# Adaptor.net
KiCad netlist of a schematic drawn in EAGLE
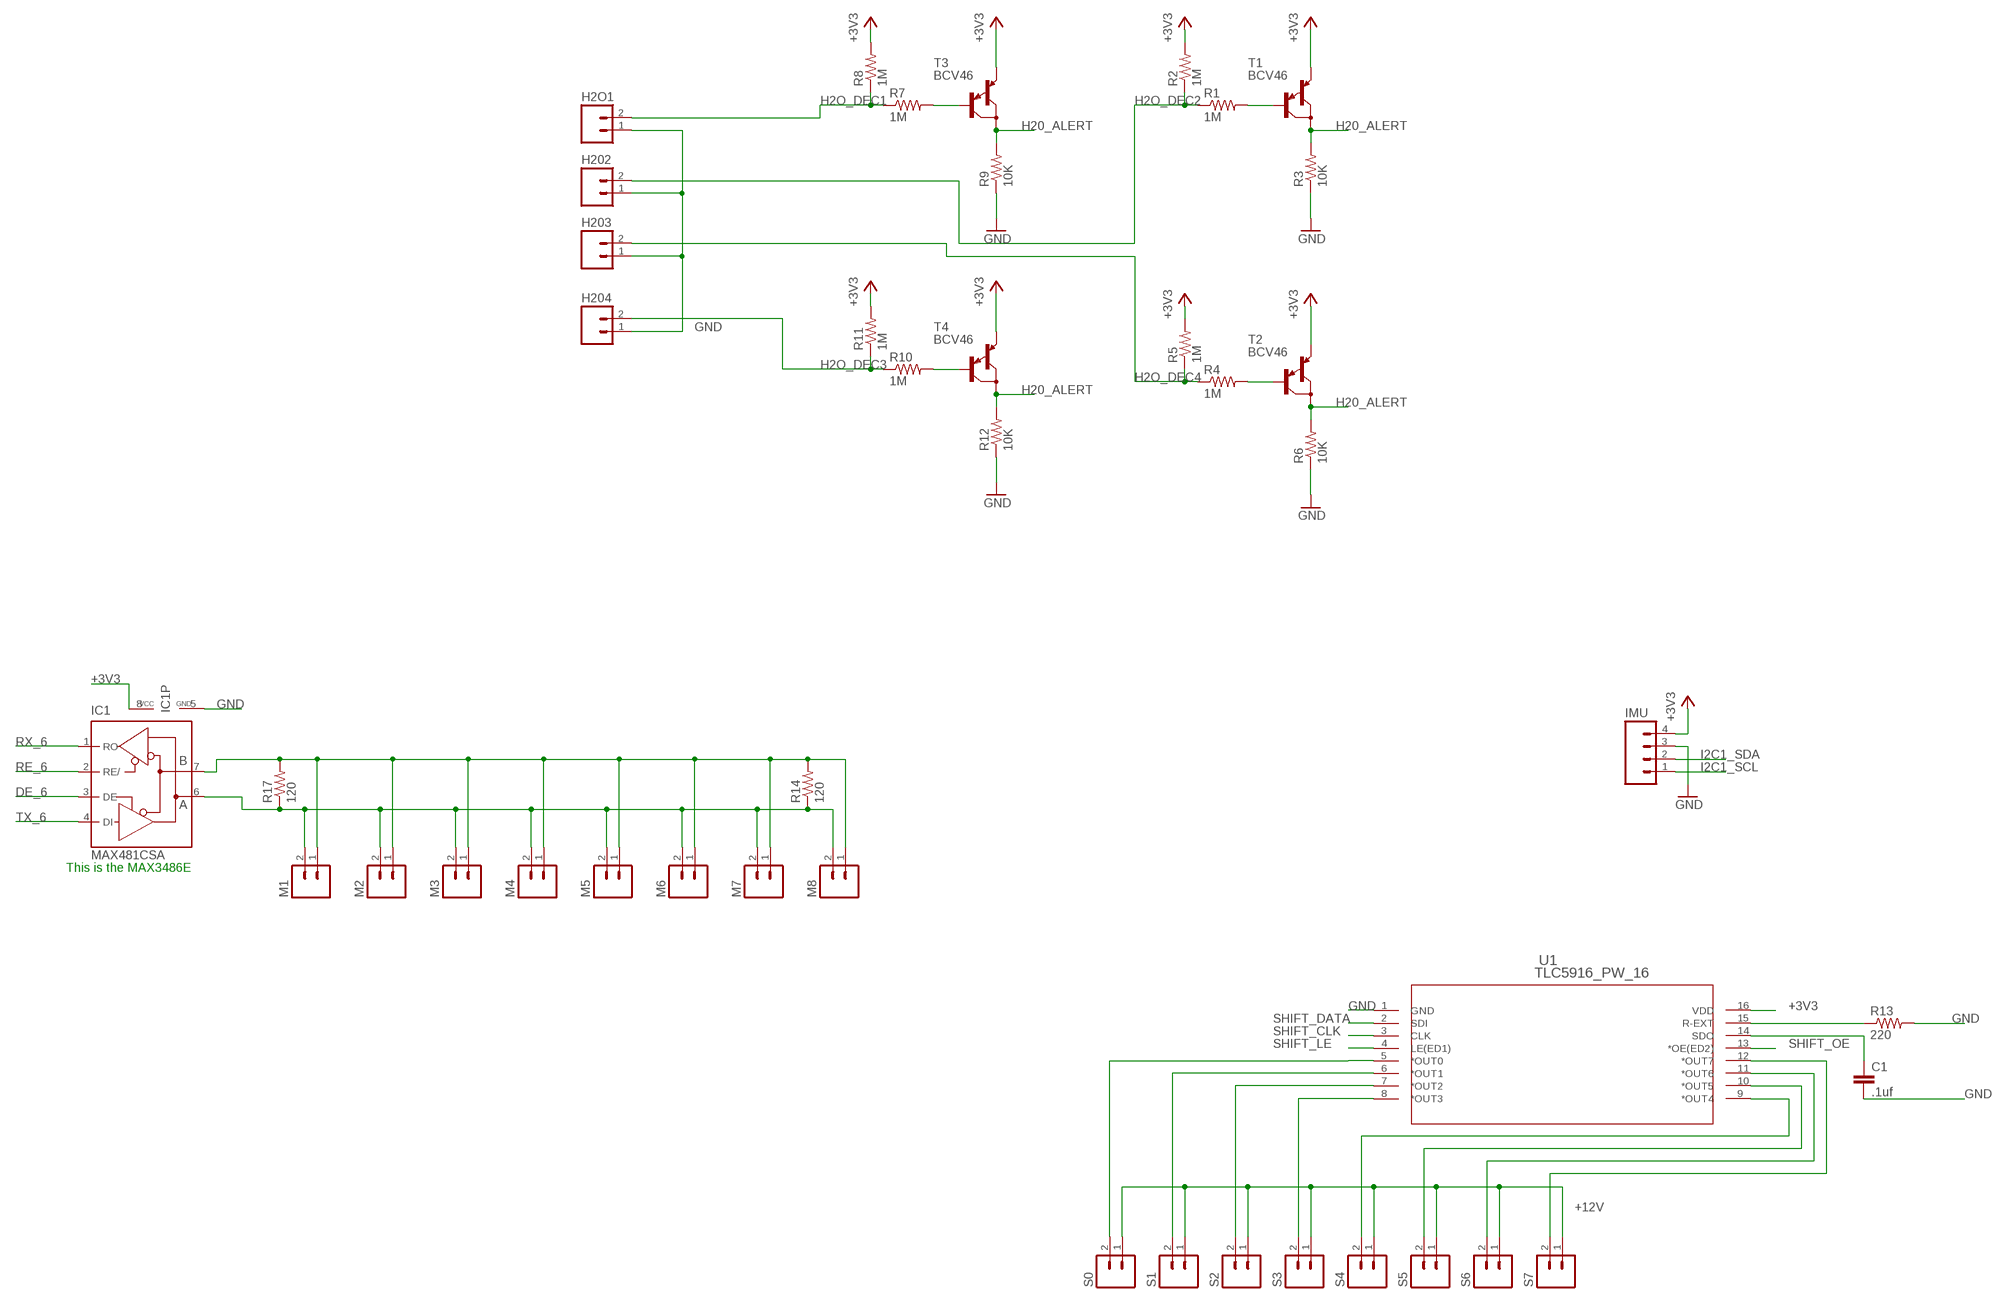
[diagram p0: schematic, sheet 1, part 1 of 2]
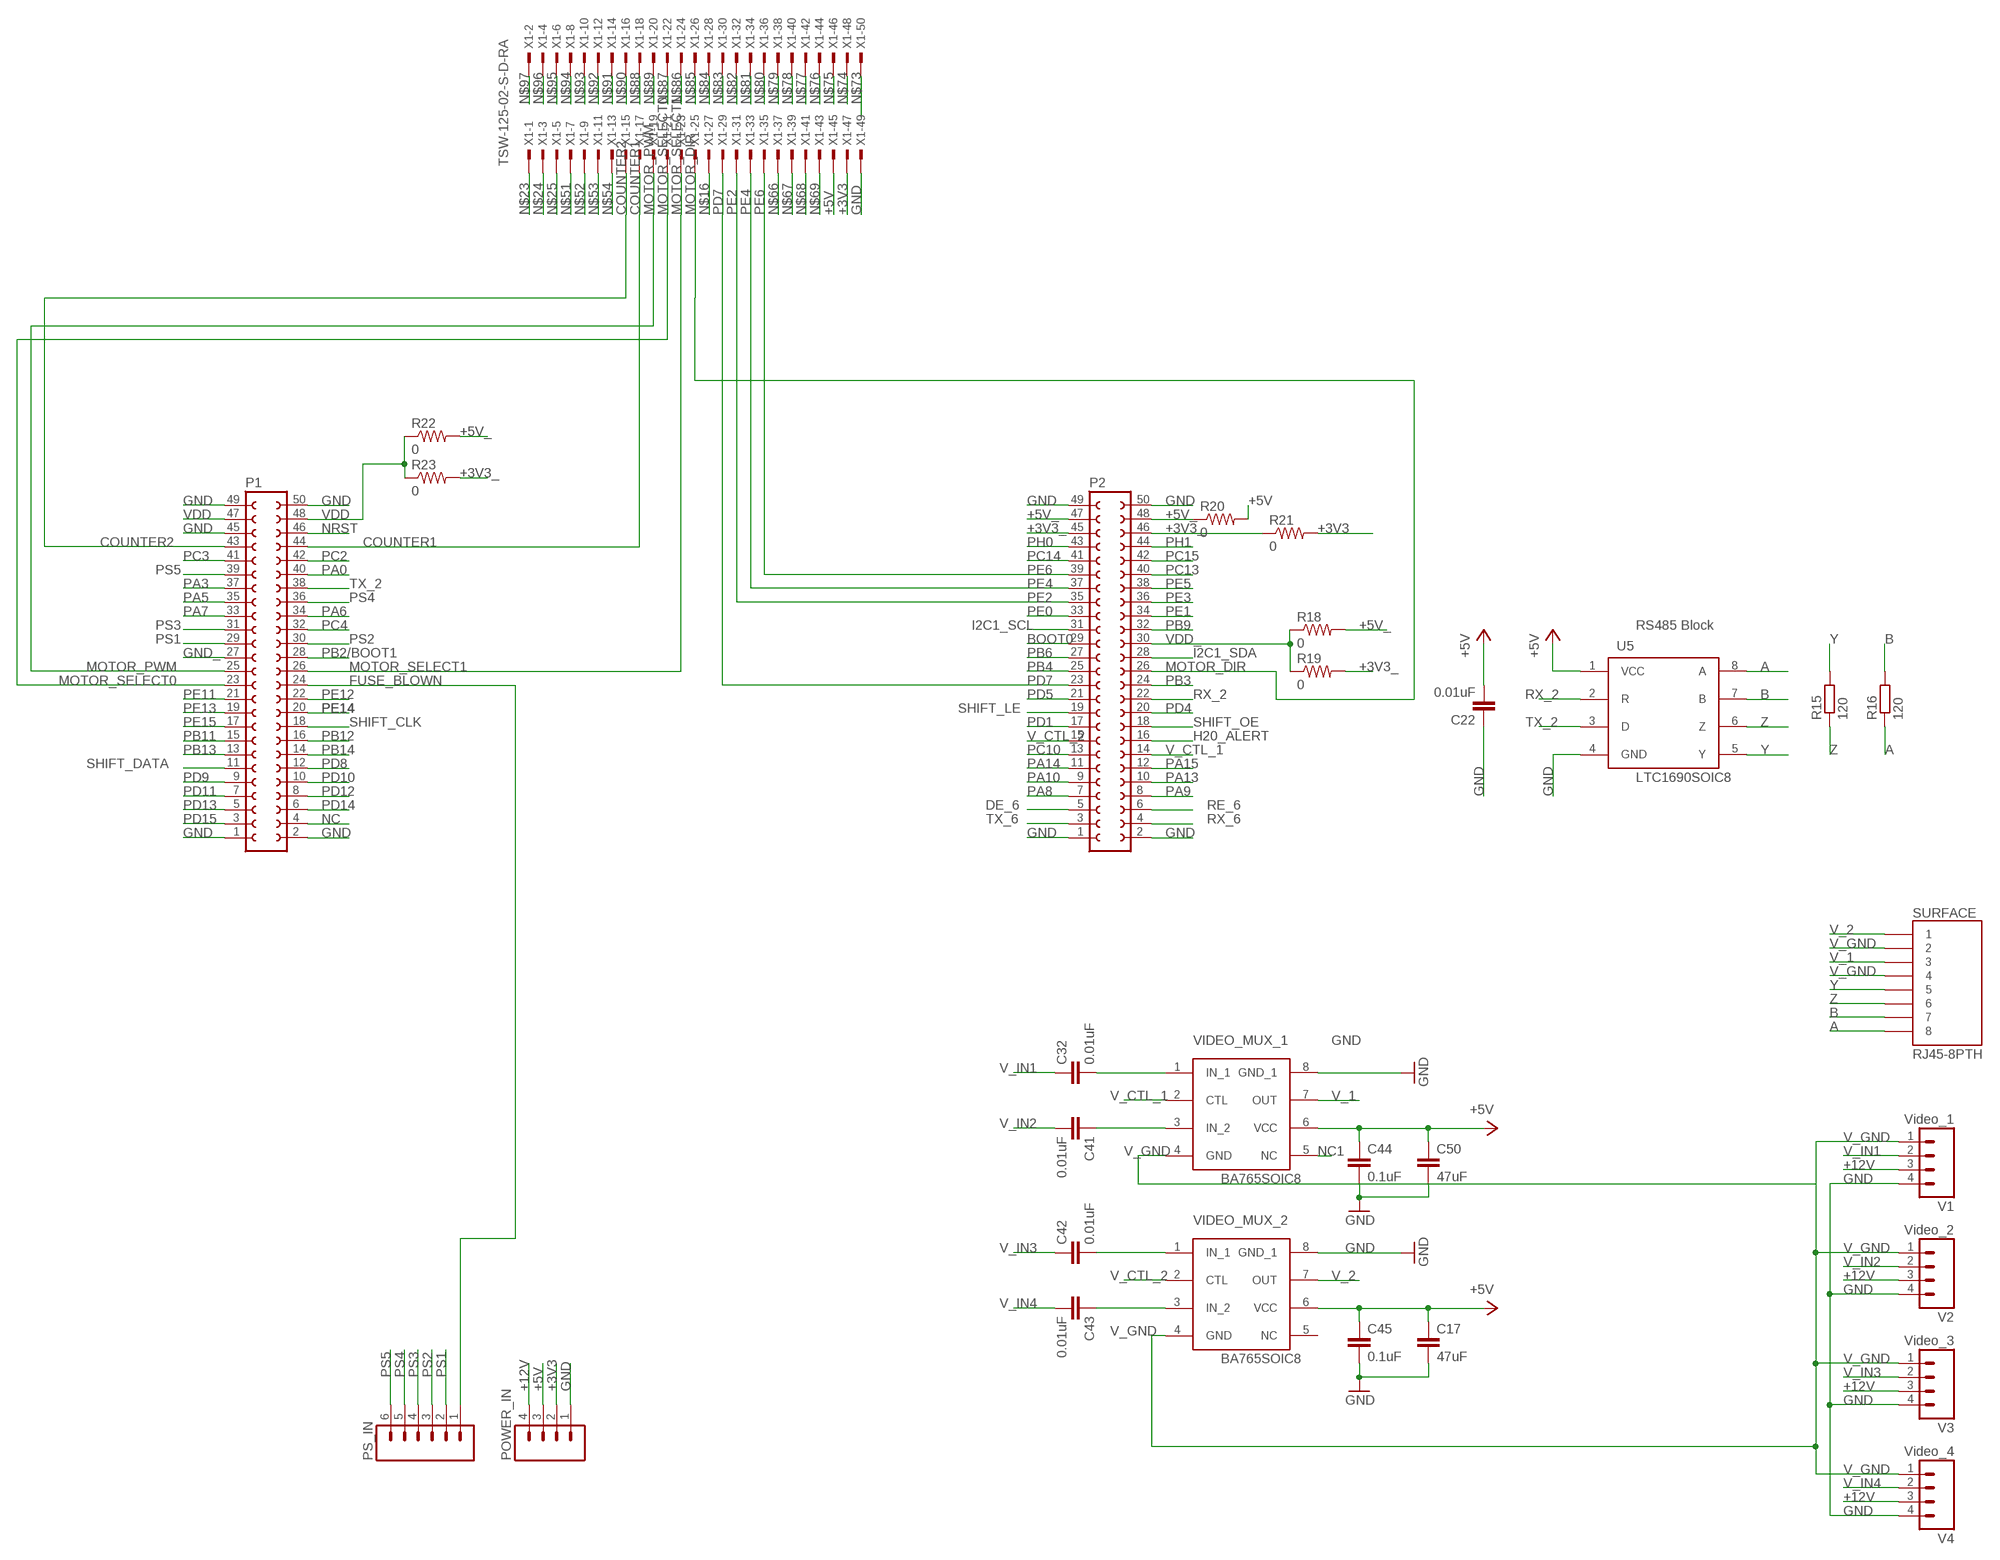
[diagram p1: schematic, sheet 1, part 2 of 2]

(export (version "E")
  (design (tool "Eeschema 10.0.6"))
  (components
    (comp (ref "C1")
      (value ".1uf")
      (footprint "eagle-import:0805")
      (libsource (lib "eagle-import") (part "CAP0805"))
    )
    (comp (ref "C17")
      (value "47uF")
      (footprint "eagle-import:C1206")
      (fields (field (name "PARTNO") "490-5528-1-ND"))
      (libsource (lib "eagle-import") (part "C-EUC1206"))
    )
    (comp (ref "C22")
      (value "0.01uF")
      (footprint "eagle-import:C0603")
      (fields (field (name "PARTNO") "478-1227-1-ND"))
      (libsource (lib "eagle-import") (part "C-EUC0603"))
    )
    (comp (ref "C32")
      (value "0.01uF")
      (footprint "eagle-import:C0603")
      (fields (field (name "PARTNO") "478-1227-1-ND"))
      (libsource (lib "eagle-import") (part "C-EUC0603"))
    )
    (comp (ref "C41")
      (value "0.01uF")
      (footprint "eagle-import:C0603")
      (fields (field (name "PARTNO") "478-1227-1-ND"))
      (libsource (lib "eagle-import") (part "C-EUC0603"))
    )
    (comp (ref "C42")
      (value "0.01uF")
      (footprint "eagle-import:C0603")
      (fields (field (name "PARTNO") "478-1227-1-ND"))
      (libsource (lib "eagle-import") (part "C-EUC0603"))
    )
    (comp (ref "C43")
      (value "0.01uF")
      (footprint "eagle-import:C0603")
      (fields (field (name "PARTNO") "478-1227-1-ND"))
      (libsource (lib "eagle-import") (part "C-EUC0603"))
    )
    (comp (ref "C44")
      (value "0.1uF")
      (footprint "eagle-import:C0603")
      (fields (field (name "PARTNO") "311-1344-1-ND"))
      (libsource (lib "eagle-import") (part "C-EUC0603"))
    )
    (comp (ref "C45")
      (value "0.1uF")
      (footprint "eagle-import:C0603")
      (fields (field (name "PARTNO") "311-1344-1-ND"))
      (libsource (lib "eagle-import") (part "C-EUC0603"))
    )
    (comp (ref "C50")
      (value "47uF")
      (footprint "eagle-import:C1206")
      (fields (field (name "PARTNO") "490-5528-1-ND"))
      (libsource (lib "eagle-import") (part "C-EUC1206"))
    )
    (comp (ref "H2O1")
      (value "M02PTH")
      (footprint "eagle-import:1X02")
      (libsource (lib "eagle-import") (part "M02PTH"))
    )
    (comp (ref "H202")
      (value "M02PTH")
      (footprint "eagle-import:1X02")
      (libsource (lib "eagle-import") (part "M02PTH"))
    )
    (comp (ref "H203")
      (value "M02PTH")
      (footprint "eagle-import:1X02")
      (libsource (lib "eagle-import") (part "M02PTH"))
    )
    (comp (ref "H204")
      (value "M02PTH")
      (footprint "eagle-import:1X02")
      (libsource (lib "eagle-import") (part "M02PTH"))
    )
    (comp (ref "IC1")
      (value "MAX481CSA")
      (footprint "eagle-import:SO08")
      (fields (field (name "MF") "MAXIM"))
      (libsource (lib "eagle-import") (part "MAX481CSA"))
    )
    (comp (ref "IMU")
      (value "M04PTH")
      (footprint "eagle-import:1X04")
      (libsource (lib "eagle-import") (part "M04PTH"))
    )
    (comp (ref "M1")
      (value "M02PTH")
      (footprint "eagle-import:1X02")
      (libsource (lib "eagle-import") (part "M02PTH"))
    )
    (comp (ref "M2")
      (value "M02PTH")
      (footprint "eagle-import:1X02")
      (libsource (lib "eagle-import") (part "M02PTH"))
    )
    (comp (ref "M3")
      (value "M02PTH")
      (footprint "eagle-import:1X02")
      (libsource (lib "eagle-import") (part "M02PTH"))
    )
    (comp (ref "M4")
      (value "M02PTH")
      (footprint "eagle-import:1X02")
      (libsource (lib "eagle-import") (part "M02PTH"))
    )
    (comp (ref "M5")
      (value "M02PTH")
      (footprint "eagle-import:1X02")
      (libsource (lib "eagle-import") (part "M02PTH"))
    )
    (comp (ref "M6")
      (value "M02PTH")
      (footprint "eagle-import:1X02")
      (libsource (lib "eagle-import") (part "M02PTH"))
    )
    (comp (ref "M7")
      (value "M02PTH")
      (footprint "eagle-import:1X02")
      (libsource (lib "eagle-import") (part "M02PTH"))
    )
    (comp (ref "M8")
      (value "M02PTH")
      (footprint "eagle-import:1X02")
      (libsource (lib "eagle-import") (part "M02PTH"))
    )
    (comp (ref "P1")
      (value "FE25-2")
      (footprint "eagle-import:FE25-2")
      (libsource (lib "eagle-import") (part "FE25-2"))
    )
    (comp (ref "P2")
      (value "FE25-2")
      (footprint "eagle-import:FE25-2")
      (libsource (lib "eagle-import") (part "FE25-2"))
    )
    (comp (ref "POWER_IN")
      (value "M04PTH")
      (footprint "eagle-import:1X04")
      (libsource (lib "eagle-import") (part "M04PTH"))
    )
    (comp (ref "PS_IN")
      (value "M06SIP")
      (footprint "eagle-import:1X06")
      (libsource (lib "eagle-import") (part "M06SIP"))
    )
    (comp (ref "R1")
      (value "1M")
      (footprint "eagle-import:0805")
      (libsource (lib "eagle-import") (part "SparkFun-Resistors_RESISTOR0805-RES"))
    )
    (comp (ref "R2")
      (value "1M")
      (footprint "eagle-import:0805")
      (libsource (lib "eagle-import") (part "SparkFun-Resistors_RESISTOR0805-RES"))
    )
    (comp (ref "R3")
      (value "10K")
      (footprint "eagle-import:0805")
      (libsource (lib "eagle-import") (part "SparkFun-Resistors_RESISTOR0805-RES"))
    )
    (comp (ref "R4")
      (value "1M")
      (footprint "eagle-import:0805")
      (libsource (lib "eagle-import") (part "SparkFun-Resistors_RESISTOR0805-RES"))
    )
    (comp (ref "R5")
      (value "1M")
      (footprint "eagle-import:0805")
      (libsource (lib "eagle-import") (part "SparkFun-Resistors_RESISTOR0805-RES"))
    )
    (comp (ref "R6")
      (value "10K")
      (footprint "eagle-import:0805")
      (libsource (lib "eagle-import") (part "SparkFun-Resistors_RESISTOR0805-RES"))
    )
    (comp (ref "R7")
      (value "1M")
      (footprint "eagle-import:0805")
      (libsource (lib "eagle-import") (part "SparkFun-Resistors_RESISTOR0805-RES"))
    )
    (comp (ref "R8")
      (value "1M")
      (footprint "eagle-import:0805")
      (libsource (lib "eagle-import") (part "SparkFun-Resistors_RESISTOR0805-RES"))
    )
    (comp (ref "R9")
      (value "10K")
      (footprint "eagle-import:0805")
      (libsource (lib "eagle-import") (part "SparkFun-Resistors_RESISTOR0805-RES"))
    )
    (comp (ref "R10")
      (value "1M")
      (footprint "eagle-import:0805")
      (libsource (lib "eagle-import") (part "SparkFun-Resistors_RESISTOR0805-RES"))
    )
    (comp (ref "R11")
      (value "1M")
      (footprint "eagle-import:0805")
      (libsource (lib "eagle-import") (part "SparkFun-Resistors_RESISTOR0805-RES"))
    )
    (comp (ref "R12")
      (value "10K")
      (footprint "eagle-import:0805")
      (libsource (lib "eagle-import") (part "SparkFun-Resistors_RESISTOR0805-RES"))
    )
    (comp (ref "R13")
      (value "220")
      (footprint "eagle-import:0805")
      (libsource (lib "eagle-import") (part "RESISTOR0805-RES"))
    )
    (comp (ref "R14")
      (value "120")
      (footprint "eagle-import:0805")
      (libsource (lib "eagle-import") (part "RESISTOR0805-RES"))
    )
    (comp (ref "R15")
      (value "120")
      (footprint "eagle-import:R0603")
      (libsource (lib "eagle-import") (part "R-EU_R0603"))
    )
    (comp (ref "R16")
      (value "120")
      (footprint "eagle-import:R0603")
      (libsource (lib "eagle-import") (part "R-EU_R0603"))
    )
    (comp (ref "R17")
      (value "120")
      (footprint "eagle-import:0805")
      (libsource (lib "eagle-import") (part "RESISTOR0805-RES"))
    )
    (comp (ref "R18")
      (value "0")
      (footprint "eagle-import:0805")
      (libsource (lib "eagle-import") (part "SparkFun-Resistors_RESISTOR0805-RES"))
    )
    (comp (ref "R19")
      (value "0")
      (footprint "eagle-import:0805")
      (libsource (lib "eagle-import") (part "SparkFun-Resistors_RESISTOR0805-RES"))
    )
    (comp (ref "R20")
      (value "0")
      (footprint "eagle-import:0805")
      (libsource (lib "eagle-import") (part "SparkFun-Resistors_RESISTOR0805-RES"))
    )
    (comp (ref "R21")
      (value "0")
      (footprint "eagle-import:0805")
      (libsource (lib "eagle-import") (part "SparkFun-Resistors_RESISTOR0805-RES"))
    )
    (comp (ref "R22")
      (value "0")
      (footprint "eagle-import:0805")
      (libsource (lib "eagle-import") (part "SparkFun-Resistors_RESISTOR0805-RES"))
    )
    (comp (ref "R23")
      (value "0")
      (footprint "eagle-import:0805")
      (libsource (lib "eagle-import") (part "SparkFun-Resistors_RESISTOR0805-RES"))
    )
    (comp (ref "S0")
      (value "M02PTH")
      (footprint "eagle-import:1X02")
      (libsource (lib "eagle-import") (part "M02PTH"))
    )
    (comp (ref "S1")
      (value "M02PTH")
      (footprint "eagle-import:1X02")
      (libsource (lib "eagle-import") (part "M02PTH"))
    )
    (comp (ref "S2")
      (value "M02PTH")
      (footprint "eagle-import:1X02")
      (libsource (lib "eagle-import") (part "M02PTH"))
    )
    (comp (ref "S3")
      (value "M02PTH")
      (footprint "eagle-import:1X02")
      (libsource (lib "eagle-import") (part "M02PTH"))
    )
    (comp (ref "S4")
      (value "M02PTH")
      (footprint "eagle-import:1X02")
      (libsource (lib "eagle-import") (part "M02PTH"))
    )
    (comp (ref "S5")
      (value "M02PTH")
      (footprint "eagle-import:1X02")
      (libsource (lib "eagle-import") (part "M02PTH"))
    )
    (comp (ref "S6")
      (value "M02PTH")
      (footprint "eagle-import:1X02")
      (libsource (lib "eagle-import") (part "M02PTH"))
    )
    (comp (ref "S7")
      (value "M02PTH")
      (footprint "eagle-import:1X02")
      (libsource (lib "eagle-import") (part "M02PTH"))
    )
    (comp (ref "SURFACE")
      (value "RJ45-8PTH")
      (footprint "eagle-import:RJ45-8")
      (libsource (lib "eagle-import") (part "RJ45-8PTH"))
    )
    (comp (ref "T1")
      (value "BCV46")
      (footprint "eagle-import:SOT23-BEC")
      (libsource (lib "eagle-import") (part "-PNP_DARL-SOT23-BECMMBTA64LT1"))
    )
    (comp (ref "T2")
      (value "BCV46")
      (footprint "eagle-import:SOT23-BEC")
      (libsource (lib "eagle-import") (part "-PNP_DARL-SOT23-BECMMBTA64LT1"))
    )
    (comp (ref "T3")
      (value "BCV46")
      (footprint "eagle-import:SOT23-BEC")
      (libsource (lib "eagle-import") (part "-PNP_DARL-SOT23-BECMMBTA64LT1"))
    )
    (comp (ref "T4")
      (value "BCV46")
      (footprint "eagle-import:SOT23-BEC")
      (libsource (lib "eagle-import") (part "-PNP_DARL-SOT23-BECMMBTA64LT1"))
    )
    (comp (ref "U1")
      (value "TLC5916_PW_16")
      (footprint "eagle-import:PW16")
      (fields
        (field (name "GENERIC_PART_NUMBER") "TLC5916")
        (field (name "MANUFACTURER") "Texas Instruments")
        (field (name "MANUFACTURER_PART_NUMBER") "tlc5916_pw_16")
      )
      (libsource (lib "eagle-import") (part "TLC5916_PW_16"))
    )
    (comp (ref "U5")
      (value "LTC1690SOIC8")
      (footprint "eagle-import:SOIC8")
      (libsource (lib "eagle-import") (part "LTC1690SOIC8"))
    )
    (comp (ref "V1")
      (value "Video_1")
      (footprint "eagle-import:1X04")
      (libsource (lib "eagle-import") (part "M04PTH"))
    )
    (comp (ref "V2")
      (value "Video_2")
      (footprint "eagle-import:1X04")
      (libsource (lib "eagle-import") (part "M04PTH"))
    )
    (comp (ref "V3")
      (value "Video_3")
      (footprint "eagle-import:1X04")
      (libsource (lib "eagle-import") (part "M04PTH"))
    )
    (comp (ref "V4")
      (value "Video_4")
      (footprint "eagle-import:1X04")
      (libsource (lib "eagle-import") (part "M04PTH"))
    )
    (comp (ref "VIDEO_MUX_1")
      (value "BA765SOIC8")
      (footprint "eagle-import:SOIC8")
      (libsource (lib "eagle-import") (part "BA765SOIC8"))
    )
    (comp (ref "VIDEO_MUX_2")
      (value "BA765SOIC8")
      (footprint "eagle-import:SOIC8")
      (libsource (lib "eagle-import") (part "BA765SOIC8"))
    )
    (comp (ref "X1")
      (value "TSW-125-02-S-D-RA")
      (footprint "eagle-import:TSW-125-02-S-D-RA")
      (libsource (lib "eagle-import") (part "TSW-125-02-S-D-RA"))
    )
  )
  (nets
    (net (code "1") (name "+3V3") (class "Default")
      (node (ref "IC1") (pin "8") (pinfunction "VCC_8") (pintype "power_in"))
      (node (ref "IMU") (pin "4") (pinfunction "4_4") (pintype "passive"))
      (node (ref "POWER_IN") (pin "2") (pinfunction "2_2") (pintype "passive"))
      (node (ref "R11") (pin "2") (pinfunction "2_2") (pintype "passive"))
      (node (ref "R2") (pin "2") (pinfunction "2_2") (pintype "passive"))
      (node (ref "R21") (pin "2") (pinfunction "2_2") (pintype "passive"))
      (node (ref "R5") (pin "2") (pinfunction "2_2") (pintype "passive"))
      (node (ref "R8") (pin "2") (pinfunction "2_2") (pintype "passive"))
      (node (ref "T1") (pin "E") (pinfunction "E_E") (pintype "passive"))
      (node (ref "T2") (pin "E") (pinfunction "E_E") (pintype "passive"))
      (node (ref "T3") (pin "E") (pinfunction "E_E") (pintype "passive"))
      (node (ref "T4") (pin "E") (pinfunction "E_E") (pintype "passive"))
      (node (ref "U1") (pin "16") (pinfunction "VDD_16") (pintype "power_in"))
      (node (ref "X1") (pin "47") (pinfunction "1_47") (pintype "passive"))
    )
    (net (code "2") (name "+5V") (class "Default")
      (node (ref "C17") (pin "1") (pinfunction "1_1") (pintype "passive"))
      (node (ref "C22") (pin "2") (pinfunction "2_2") (pintype "passive"))
      (node (ref "C44") (pin "1") (pinfunction "1_1") (pintype "passive"))
      (node (ref "C45") (pin "1") (pinfunction "1_1") (pintype "passive"))
      (node (ref "C50") (pin "1") (pinfunction "1_1") (pintype "passive"))
      (node (ref "POWER_IN") (pin "3") (pinfunction "3_3") (pintype "passive"))
      (node (ref "R20") (pin "2") (pinfunction "2_2") (pintype "passive"))
      (node (ref "U5") (pin "1") (pinfunction "VCC_1") (pintype "power_in"))
      (node (ref "VIDEO_MUX_1") (pin "6") (pinfunction "VCC_6") (pintype "bidirectional"))
      (node (ref "VIDEO_MUX_2") (pin "6") (pinfunction "VCC_6") (pintype "bidirectional"))
      (node (ref "X1") (pin "45") (pinfunction "1_45") (pintype "passive"))
    )
    (net (code "3") (name "/+3V3_") (class "Default")
      (node (ref "P2") (pin "45") (pinfunction "45_45") (pintype "passive"))
      (node (ref "P2") (pin "46") (pinfunction "46_46") (pintype "passive"))
      (node (ref "R19") (pin "2") (pinfunction "2_2") (pintype "passive"))
      (node (ref "R21") (pin "1") (pinfunction "1_1") (pintype "passive"))
      (node (ref "R23") (pin "2") (pinfunction "2_2") (pintype "passive"))
    )
    (net (code "4") (name "/+5V_") (class "Default")
      (node (ref "P2") (pin "47") (pinfunction "47_47") (pintype "passive"))
      (node (ref "P2") (pin "48") (pinfunction "48_48") (pintype "passive"))
      (node (ref "R18") (pin "2") (pinfunction "2_2") (pintype "passive"))
      (node (ref "R20") (pin "1") (pinfunction "1_1") (pintype "passive"))
      (node (ref "R22") (pin "2") (pinfunction "2_2") (pintype "passive"))
    )
    (net (code "5") (name "/+12V") (class "Default")
      (node (ref "POWER_IN") (pin "4") (pinfunction "4_4") (pintype "passive"))
      (node (ref "S0") (pin "1") (pinfunction "1_1") (pintype "passive"))
      (node (ref "S1") (pin "1") (pinfunction "1_1") (pintype "passive"))
      (node (ref "S2") (pin "1") (pinfunction "1_1") (pintype "passive"))
      (node (ref "S3") (pin "1") (pinfunction "1_1") (pintype "passive"))
      (node (ref "S4") (pin "1") (pinfunction "1_1") (pintype "passive"))
      (node (ref "S5") (pin "1") (pinfunction "1_1") (pintype "passive"))
      (node (ref "S6") (pin "1") (pinfunction "1_1") (pintype "passive"))
      (node (ref "S7") (pin "1") (pinfunction "1_1") (pintype "passive"))
      (node (ref "V1") (pin "3") (pinfunction "3_3") (pintype "passive"))
      (node (ref "V2") (pin "3") (pinfunction "3_3") (pintype "passive"))
      (node (ref "V3") (pin "3") (pinfunction "3_3") (pintype "passive"))
      (node (ref "V4") (pin "3") (pinfunction "3_3") (pintype "passive"))
    )
    (net (code "6") (name "/A") (class "Default")
      (node (ref "R16") (pin "1") (pinfunction "1_1") (pintype "passive"))
      (node (ref "SURFACE") (pin "8") (pinfunction "8_8") (pintype "bidirectional"))
      (node (ref "U5") (pin "8") (pinfunction "A_8") (pintype "bidirectional"))
    )
    (net (code "7") (name "/B") (class "Default")
      (node (ref "R16") (pin "2") (pinfunction "2_2") (pintype "passive"))
      (node (ref "SURFACE") (pin "7") (pinfunction "7_7") (pintype "bidirectional"))
      (node (ref "U5") (pin "7") (pinfunction "B_7") (pintype "bidirectional"))
    )
    (net (code "8") (name "/BOOT0") (class "Default")
      (node (ref "P2") (pin "29") (pinfunction "29_29") (pintype "passive"))
    )
    (net (code "9") (name "/COUNTER1") (class "Default")
      (node (ref "P1") (pin "44") (pinfunction "44_44") (pintype "passive"))
      (node (ref "X1") (pin "17") (pinfunction "1_17") (pintype "passive"))
    )
    (net (code "10") (name "/COUNTER2") (class "Default")
      (node (ref "P1") (pin "43") (pinfunction "43_43") (pintype "passive"))
      (node (ref "X1") (pin "15") (pinfunction "1_15") (pintype "passive"))
    )
    (net (code "11") (name "/DE_6") (class "Default")
      (node (ref "IC1") (pin "3") (pinfunction "DE_3") (pintype "input"))
      (node (ref "P2") (pin "5") (pinfunction "5_5") (pintype "passive"))
    )
    (net (code "12") (name "/FUSE_BLOWN") (class "Default")
      (node (ref "P1") (pin "24") (pinfunction "24_24") (pintype "passive"))
      (node (ref "PS_IN") (pin "1") (pinfunction "1_1") (pintype "passive"))
    )
    (net (code "13") (name "/GND_") (class "Default")
      (node (ref "P1") (pin "27") (pinfunction "27_27") (pintype "passive"))
    )
    (net (code "14") (name "/H2O_DEC1") (class "Default")
      (node (ref "H2O1") (pin "2") (pinfunction "2_2") (pintype "passive"))
      (node (ref "R7") (pin "1") (pinfunction "1_1") (pintype "passive"))
      (node (ref "R8") (pin "1") (pinfunction "1_1") (pintype "passive"))
    )
    (net (code "15") (name "/H2O_DEC2") (class "Default")
      (node (ref "H202") (pin "2") (pinfunction "2_2") (pintype "passive"))
      (node (ref "R1") (pin "1") (pinfunction "1_1") (pintype "passive"))
      (node (ref "R2") (pin "1") (pinfunction "1_1") (pintype "passive"))
    )
    (net (code "16") (name "/H2O_DEC3") (class "Default")
      (node (ref "H204") (pin "2") (pinfunction "2_2") (pintype "passive"))
      (node (ref "R10") (pin "1") (pinfunction "1_1") (pintype "passive"))
      (node (ref "R11") (pin "1") (pinfunction "1_1") (pintype "passive"))
    )
    (net (code "17") (name "/H2O_DEC4") (class "Default")
      (node (ref "H203") (pin "2") (pinfunction "2_2") (pintype "passive"))
      (node (ref "R4") (pin "1") (pinfunction "1_1") (pintype "passive"))
      (node (ref "R5") (pin "1") (pinfunction "1_1") (pintype "passive"))
    )
    (net (code "18") (name "/H20_ALERT") (class "Default")
      (node (ref "P2") (pin "16") (pinfunction "16_16") (pintype "passive"))
      (node (ref "R12") (pin "2") (pinfunction "2_2") (pintype "passive"))
      (node (ref "R3") (pin "2") (pinfunction "2_2") (pintype "passive"))
      (node (ref "R6") (pin "2") (pinfunction "2_2") (pintype "passive"))
      (node (ref "R9") (pin "2") (pinfunction "2_2") (pintype "passive"))
      (node (ref "T1") (pin "C") (pinfunction "C_C") (pintype "passive"))
      (node (ref "T2") (pin "C") (pinfunction "C_C") (pintype "passive"))
      (node (ref "T3") (pin "C") (pinfunction "C_C") (pintype "passive"))
      (node (ref "T4") (pin "C") (pinfunction "C_C") (pintype "passive"))
    )
    (net (code "19") (name "/I2C1_SCL") (class "Default")
      (node (ref "IMU") (pin "1") (pinfunction "1_1") (pintype "passive"))
      (node (ref "P2") (pin "31") (pinfunction "31_31") (pintype "passive"))
    )
    (net (code "20") (name "/I2C1_SDA") (class "Default")
      (node (ref "IMU") (pin "2") (pinfunction "2_2") (pintype "passive"))
      (node (ref "P2") (pin "28") (pinfunction "28_28") (pintype "passive"))
    )
    (net (code "21") (name "/MOTOR_DIR") (class "Default")
      (node (ref "P2") (pin "26") (pinfunction "26_26") (pintype "passive"))
      (node (ref "X1") (pin "25") (pinfunction "1_25") (pintype "passive"))
    )
    (net (code "22") (name "/MOTOR_PWM") (class "Default")
      (node (ref "P1") (pin "25") (pinfunction "25_25") (pintype "passive"))
      (node (ref "X1") (pin "19") (pinfunction "1_19") (pintype "passive"))
    )
    (net (code "23") (name "/MOTOR_SELECT0") (class "Default")
      (node (ref "P1") (pin "23") (pinfunction "23_23") (pintype "passive"))
      (node (ref "X1") (pin "21") (pinfunction "1_21") (pintype "passive"))
    )
    (net (code "24") (name "/MOTOR_SELECT1") (class "Default")
      (node (ref "P1") (pin "26") (pinfunction "26_26") (pintype "passive"))
      (node (ref "X1") (pin "23") (pinfunction "1_23") (pintype "passive"))
    )
    (net (code "25") (name "/N$16") (class "Default")
      (node (ref "X1") (pin "27") (pinfunction "1_27") (pintype "passive"))
    )
    (net (code "26") (name "/N$23") (class "Default")
      (node (ref "X1") (pin "1") (pinfunction "1_1") (pintype "passive"))
    )
    (net (code "27") (name "/N$24") (class "Default")
      (node (ref "X1") (pin "3") (pinfunction "1_3") (pintype "passive"))
    )
    (net (code "28") (name "/N$25") (class "Default")
      (node (ref "X1") (pin "5") (pinfunction "1_5") (pintype "passive"))
    )
    (net (code "29") (name "/N$51") (class "Default")
      (node (ref "X1") (pin "7") (pinfunction "1_7") (pintype "passive"))
    )
    (net (code "30") (name "/N$52") (class "Default")
      (node (ref "X1") (pin "9") (pinfunction "1_9") (pintype "passive"))
    )
    (net (code "31") (name "/N$53") (class "Default")
      (node (ref "X1") (pin "11") (pinfunction "1_11") (pintype "passive"))
    )
    (net (code "32") (name "/N$54") (class "Default")
      (node (ref "X1") (pin "13") (pinfunction "1_13") (pintype "passive"))
    )
    (net (code "33") (name "/N$66") (class "Default")
      (node (ref "X1") (pin "37") (pinfunction "1_37") (pintype "passive"))
    )
    (net (code "34") (name "/N$67") (class "Default")
      (node (ref "X1") (pin "39") (pinfunction "1_39") (pintype "passive"))
    )
    (net (code "35") (name "/N$68") (class "Default")
      (node (ref "X1") (pin "41") (pinfunction "1_41") (pintype "passive"))
    )
    (net (code "36") (name "/N$69") (class "Default")
      (node (ref "X1") (pin "43") (pinfunction "1_43") (pintype "passive"))
    )
    (net (code "37") (name "/N$73") (class "Default")
      (node (ref "X1") (pin "50") (pinfunction "1_50") (pintype "passive"))
    )
    (net (code "38") (name "/N$74") (class "Default")
      (node (ref "X1") (pin "48") (pinfunction "1_48") (pintype "passive"))
    )
    (net (code "39") (name "/N$75") (class "Default")
      (node (ref "X1") (pin "46") (pinfunction "1_46") (pintype "passive"))
    )
    (net (code "40") (name "/N$76") (class "Default")
      (node (ref "X1") (pin "44") (pinfunction "1_44") (pintype "passive"))
    )
    (net (code "41") (name "/N$77") (class "Default")
      (node (ref "X1") (pin "42") (pinfunction "1_42") (pintype "passive"))
    )
    (net (code "42") (name "/N$78") (class "Default")
      (node (ref "X1") (pin "40") (pinfunction "1_40") (pintype "passive"))
    )
    (net (code "43") (name "/N$79") (class "Default")
      (node (ref "X1") (pin "38") (pinfunction "1_38") (pintype "passive"))
    )
    (net (code "44") (name "/N$80") (class "Default")
      (node (ref "X1") (pin "36") (pinfunction "1_36") (pintype "passive"))
    )
    (net (code "45") (name "/N$81") (class "Default")
      (node (ref "X1") (pin "34") (pinfunction "1_34") (pintype "passive"))
    )
    (net (code "46") (name "/N$82") (class "Default")
      (node (ref "X1") (pin "32") (pinfunction "1_32") (pintype "passive"))
    )
    (net (code "47") (name "/N$83") (class "Default")
      (node (ref "X1") (pin "30") (pinfunction "1_30") (pintype "passive"))
    )
    (net (code "48") (name "/N$84") (class "Default")
      (node (ref "X1") (pin "28") (pinfunction "1_28") (pintype "passive"))
    )
    (net (code "49") (name "/N$85") (class "Default")
      (node (ref "X1") (pin "26") (pinfunction "1_26") (pintype "passive"))
    )
    (net (code "50") (name "/N$86") (class "Default")
      (node (ref "X1") (pin "24") (pinfunction "1_24") (pintype "passive"))
    )
    (net (code "51") (name "/N$87") (class "Default")
      (node (ref "X1") (pin "22") (pinfunction "1_22") (pintype "passive"))
    )
    (net (code "52") (name "/N$88") (class "Default")
      (node (ref "X1") (pin "18") (pinfunction "1_18") (pintype "passive"))
    )
    (net (code "53") (name "/N$89") (class "Default")
      (node (ref "X1") (pin "20") (pinfunction "1_20") (pintype "passive"))
    )
    (net (code "54") (name "/N$90") (class "Default")
      (node (ref "X1") (pin "16") (pinfunction "1_16") (pintype "passive"))
    )
    (net (code "55") (name "/N$91") (class "Default")
      (node (ref "X1") (pin "14") (pinfunction "1_14") (pintype "passive"))
    )
    (net (code "56") (name "/N$92") (class "Default")
      (node (ref "X1") (pin "12") (pinfunction "1_12") (pintype "passive"))
    )
    (net (code "57") (name "/N$93") (class "Default")
      (node (ref "X1") (pin "10") (pinfunction "1_10") (pintype "passive"))
    )
    (net (code "58") (name "/N$94") (class "Default")
      (node (ref "X1") (pin "8") (pinfunction "1_8") (pintype "passive"))
    )
    (net (code "59") (name "/N$95") (class "Default")
      (node (ref "X1") (pin "6") (pinfunction "1_6") (pintype "passive"))
    )
    (net (code "60") (name "/N$96") (class "Default")
      (node (ref "X1") (pin "4") (pinfunction "1_4") (pintype "passive"))
    )
    (net (code "61") (name "/N$97") (class "Default")
      (node (ref "X1") (pin "2") (pinfunction "1_2") (pintype "passive"))
    )
    (net (code "62") (name "/NC") (class "Default")
      (node (ref "P1") (pin "4") (pinfunction "4_4") (pintype "passive"))
    )
    (net (code "63") (name "/NC1") (class "Default")
      (node (ref "VIDEO_MUX_1") (pin "5") (pinfunction "NC_5") (pintype "bidirectional"))
    )
    (net (code "64") (name "/NRST") (class "Default")
      (node (ref "P1") (pin "46") (pinfunction "46_46") (pintype "passive"))
    )
    (net (code "65") (name "/PA0") (class "Default")
      (node (ref "P1") (pin "40") (pinfunction "40_40") (pintype "passive"))
    )
    (net (code "66") (name "/PA3") (class "Default")
      (node (ref "P1") (pin "37") (pinfunction "37_37") (pintype "passive"))
    )
    (net (code "67") (name "/PA5") (class "Default")
      (node (ref "P1") (pin "35") (pinfunction "35_35") (pintype "passive"))
    )
    (net (code "68") (name "/PA6") (class "Default")
      (node (ref "P1") (pin "34") (pinfunction "34_34") (pintype "passive"))
    )
    (net (code "69") (name "/PA7") (class "Default")
      (node (ref "P1") (pin "33") (pinfunction "33_33") (pintype "passive"))
    )
    (net (code "70") (name "/PA8") (class "Default")
      (node (ref "P2") (pin "7") (pinfunction "7_7") (pintype "passive"))
    )
    (net (code "71") (name "/PA9") (class "Default")
      (node (ref "P2") (pin "8") (pinfunction "8_8") (pintype "passive"))
    )
    (net (code "72") (name "/PA10") (class "Default")
      (node (ref "P2") (pin "9") (pinfunction "9_9") (pintype "passive"))
    )
    (net (code "73") (name "/PA13") (class "Default")
      (node (ref "P2") (pin "10") (pinfunction "10_10") (pintype "passive"))
    )
    (net (code "74") (name "/PA14") (class "Default")
      (node (ref "P2") (pin "11") (pinfunction "11_11") (pintype "passive"))
    )
    (net (code "75") (name "/PA15") (class "Default")
      (node (ref "P2") (pin "12") (pinfunction "12_12") (pintype "passive"))
    )
    (net (code "76") (name "/PB2{slash}BOOT1") (class "Default")
      (node (ref "P1") (pin "28") (pinfunction "28_28") (pintype "passive"))
    )
    (net (code "77") (name "/PB3") (class "Default")
      (node (ref "P2") (pin "24") (pinfunction "24_24") (pintype "passive"))
    )
    (net (code "78") (name "/PB4") (class "Default")
      (node (ref "P2") (pin "25") (pinfunction "25_25") (pintype "passive"))
    )
    (net (code "79") (name "/PB6") (class "Default")
      (node (ref "P2") (pin "27") (pinfunction "27_27") (pintype "passive"))
    )
    (net (code "80") (name "/PB9") (class "Default")
      (node (ref "P2") (pin "32") (pinfunction "32_32") (pintype "passive"))
    )
    (net (code "81") (name "/PB11") (class "Default")
      (node (ref "P1") (pin "15") (pinfunction "15_15") (pintype "passive"))
    )
    (net (code "82") (name "/PB12") (class "Default")
      (node (ref "P1") (pin "16") (pinfunction "16_16") (pintype "passive"))
    )
    (net (code "83") (name "/PB13") (class "Default")
      (node (ref "P1") (pin "13") (pinfunction "13_13") (pintype "passive"))
    )
    (net (code "84") (name "/PB14") (class "Default")
      (node (ref "P1") (pin "14") (pinfunction "14_14") (pintype "passive"))
    )
    (net (code "85") (name "/PC2") (class "Default")
      (node (ref "P1") (pin "42") (pinfunction "42_42") (pintype "passive"))
    )
    (net (code "86") (name "/PC3") (class "Default")
      (node (ref "P1") (pin "41") (pinfunction "41_41") (pintype "passive"))
    )
    (net (code "87") (name "/PC4") (class "Default")
      (node (ref "P1") (pin "32") (pinfunction "32_32") (pintype "passive"))
    )
    (net (code "88") (name "/PC10") (class "Default")
      (node (ref "P2") (pin "13") (pinfunction "13_13") (pintype "passive"))
    )
    (net (code "89") (name "/PC13") (class "Default")
      (node (ref "P2") (pin "40") (pinfunction "40_40") (pintype "passive"))
    )
    (net (code "90") (name "/PC14") (class "Default")
      (node (ref "P2") (pin "41") (pinfunction "41_41") (pintype "passive"))
    )
    (net (code "91") (name "/PC15") (class "Default")
      (node (ref "P2") (pin "42") (pinfunction "42_42") (pintype "passive"))
    )
    (net (code "92") (name "/PD1") (class "Default")
      (node (ref "P2") (pin "17") (pinfunction "17_17") (pintype "passive"))
    )
    (net (code "93") (name "/PD4") (class "Default")
      (node (ref "P2") (pin "20") (pinfunction "20_20") (pintype "passive"))
    )
    (net (code "94") (name "/PD5") (class "Default")
      (node (ref "P2") (pin "21") (pinfunction "21_21") (pintype "passive"))
    )
    (net (code "95") (name "/PD7") (class "Default")
      (node (ref "P2") (pin "23") (pinfunction "23_23") (pintype "passive"))
      (node (ref "X1") (pin "29") (pinfunction "1_29") (pintype "passive"))
    )
    (net (code "96") (name "/PD8") (class "Default")
      (node (ref "P1") (pin "12") (pinfunction "12_12") (pintype "passive"))
    )
    (net (code "97") (name "/PD9") (class "Default")
      (node (ref "P1") (pin "9") (pinfunction "9_9") (pintype "passive"))
    )
    (net (code "98") (name "/PD10") (class "Default")
      (node (ref "P1") (pin "10") (pinfunction "10_10") (pintype "passive"))
    )
    (net (code "99") (name "/PD11") (class "Default")
      (node (ref "P1") (pin "7") (pinfunction "7_7") (pintype "passive"))
    )
    (net (code "100") (name "/PD12") (class "Default")
      (node (ref "P1") (pin "8") (pinfunction "8_8") (pintype "passive"))
    )
    (net (code "101") (name "/PD13") (class "Default")
      (node (ref "P1") (pin "5") (pinfunction "5_5") (pintype "passive"))
    )
    (net (code "102") (name "/PD14") (class "Default")
      (node (ref "P1") (pin "6") (pinfunction "6_6") (pintype "passive"))
    )
    (net (code "103") (name "/PD15") (class "Default")
      (node (ref "P1") (pin "3") (pinfunction "3_3") (pintype "passive"))
    )
    (net (code "104") (name "/PE0") (class "Default")
      (node (ref "P2") (pin "33") (pinfunction "33_33") (pintype "passive"))
    )
    (net (code "105") (name "/PE1") (class "Default")
      (node (ref "P2") (pin "34") (pinfunction "34_34") (pintype "passive"))
    )
    (net (code "106") (name "/PE2") (class "Default")
      (node (ref "P2") (pin "35") (pinfunction "35_35") (pintype "passive"))
      (node (ref "X1") (pin "31") (pinfunction "1_31") (pintype "passive"))
    )
    (net (code "107") (name "/PE3") (class "Default")
      (node (ref "P2") (pin "36") (pinfunction "36_36") (pintype "passive"))
    )
    (net (code "108") (name "/PE4") (class "Default")
      (node (ref "P2") (pin "37") (pinfunction "37_37") (pintype "passive"))
      (node (ref "X1") (pin "33") (pinfunction "1_33") (pintype "passive"))
    )
    (net (code "109") (name "/PE5") (class "Default")
      (node (ref "P2") (pin "38") (pinfunction "38_38") (pintype "passive"))
    )
    (net (code "110") (name "/PE6") (class "Default")
      (node (ref "P2") (pin "39") (pinfunction "39_39") (pintype "passive"))
      (node (ref "X1") (pin "35") (pinfunction "1_35") (pintype "passive"))
    )
    (net (code "111") (name "/PE11") (class "Default")
      (node (ref "P1") (pin "21") (pinfunction "21_21") (pintype "passive"))
    )
    (net (code "112") (name "/PE12") (class "Default")
      (node (ref "P1") (pin "22") (pinfunction "22_22") (pintype "passive"))
    )
    (net (code "113") (name "/PE13") (class "Default")
      (node (ref "P1") (pin "19") (pinfunction "19_19") (pintype "passive"))
    )
    (net (code "114") (name "/PE14") (class "Default")
      (node (ref "P1") (pin "20") (pinfunction "20_20") (pintype "passive"))
    )
    (net (code "115") (name "/PE15") (class "Default")
      (node (ref "P1") (pin "17") (pinfunction "17_17") (pintype "passive"))
    )
    (net (code "116") (name "/PH0") (class "Default")
      (node (ref "P2") (pin "43") (pinfunction "43_43") (pintype "passive"))
    )
    (net (code "117") (name "/PH1") (class "Default")
      (node (ref "P2") (pin "44") (pinfunction "44_44") (pintype "passive"))
    )
    (net (code "118") (name "/PS1") (class "Default")
      (node (ref "P1") (pin "29") (pinfunction "29_29") (pintype "passive"))
      (node (ref "PS_IN") (pin "2") (pinfunction "2_2") (pintype "passive"))
    )
    (net (code "119") (name "/PS2") (class "Default")
      (node (ref "P1") (pin "30") (pinfunction "30_30") (pintype "passive"))
      (node (ref "PS_IN") (pin "3") (pinfunction "3_3") (pintype "passive"))
    )
    (net (code "120") (name "/PS3") (class "Default")
      (node (ref "P1") (pin "31") (pinfunction "31_31") (pintype "passive"))
      (node (ref "PS_IN") (pin "4") (pinfunction "4_4") (pintype "passive"))
    )
    (net (code "121") (name "/PS4") (class "Default")
      (node (ref "P1") (pin "36") (pinfunction "36_36") (pintype "passive"))
      (node (ref "PS_IN") (pin "5") (pinfunction "5_5") (pintype "passive"))
    )
    (net (code "122") (name "/PS5") (class "Default")
      (node (ref "P1") (pin "39") (pinfunction "39_39") (pintype "passive"))
      (node (ref "PS_IN") (pin "6") (pinfunction "6_6") (pintype "passive"))
    )
    (net (code "123") (name "/RE_6") (class "Default")
      (node (ref "IC1") (pin "2") (pinfunction "RE/_2") (pintype "input"))
      (node (ref "P2") (pin "6") (pinfunction "6_6") (pintype "passive"))
    )
    (net (code "124") (name "/RX_2") (class "Default")
      (node (ref "P2") (pin "22") (pinfunction "22_22") (pintype "passive"))
      (node (ref "U5") (pin "2") (pinfunction "R_2") (pintype "bidirectional"))
    )
    (net (code "125") (name "/RX_6") (class "Default")
      (node (ref "IC1") (pin "1") (pinfunction "RO_1") (pintype "output"))
      (node (ref "P2") (pin "4") (pinfunction "4_4") (pintype "passive"))
    )
    (net (code "126") (name "/SHIFT_CLK") (class "Default")
      (node (ref "P1") (pin "18") (pinfunction "18_18") (pintype "passive"))
      (node (ref "U1") (pin "3") (pinfunction "CLK_3") (pintype "input"))
    )
    (net (code "127") (name "/SHIFT_DATA") (class "Default")
      (node (ref "P1") (pin "11") (pinfunction "11_11") (pintype "passive"))
      (node (ref "U1") (pin "2") (pinfunction "SDI_2") (pintype "input"))
    )
    (net (code "128") (name "/SHIFT_LE") (class "Default")
      (node (ref "P2") (pin "19") (pinfunction "19_19") (pintype "passive"))
      (node (ref "U1") (pin "4") (pinfunction "LE(ED1)_4") (pintype "input"))
    )
    (net (code "129") (name "/SHIFT_OE") (class "Default")
      (node (ref "P2") (pin "18") (pinfunction "18_18") (pintype "passive"))
      (node (ref "U1") (pin "13") (pinfunction "*OE(ED2)_13") (pintype "output"))
    )
    (net (code "130") (name "/TX_2") (class "Default")
      (node (ref "P1") (pin "38") (pinfunction "38_38") (pintype "passive"))
      (node (ref "U5") (pin "3") (pinfunction "D_3") (pintype "bidirectional"))
    )
    (net (code "131") (name "/TX_6") (class "Default")
      (node (ref "IC1") (pin "4") (pinfunction "DI_4") (pintype "input"))
      (node (ref "P2") (pin "3") (pinfunction "3_3") (pintype "passive"))
    )
    (net (code "132") (name "/VDD") (class "Default")
      (node (ref "P1") (pin "47") (pinfunction "47_47") (pintype "passive"))
      (node (ref "P1") (pin "48") (pinfunction "48_48") (pintype "passive"))
      (node (ref "R22") (pin "1") (pinfunction "1_1") (pintype "passive"))
      (node (ref "R23") (pin "1") (pinfunction "1_1") (pintype "passive"))
    )
    (net (code "133") (name "/VDD_") (class "Default")
      (node (ref "P2") (pin "30") (pinfunction "30_30") (pintype "passive"))
      (node (ref "R18") (pin "1") (pinfunction "1_1") (pintype "passive"))
      (node (ref "R19") (pin "1") (pinfunction "1_1") (pintype "passive"))
    )
    (net (code "134") (name "/V_1") (class "Default")
      (node (ref "SURFACE") (pin "3") (pinfunction "3_3") (pintype "bidirectional"))
      (node (ref "VIDEO_MUX_1") (pin "7") (pinfunction "OUT_7") (pintype "bidirectional"))
    )
    (net (code "135") (name "/V_2") (class "Default")
      (node (ref "SURFACE") (pin "1") (pinfunction "1_1") (pintype "bidirectional"))
      (node (ref "VIDEO_MUX_2") (pin "7") (pinfunction "OUT_7") (pintype "bidirectional"))
    )
    (net (code "136") (name "/V_CTL_1") (class "Default")
      (node (ref "P2") (pin "14") (pinfunction "14_14") (pintype "passive"))
      (node (ref "VIDEO_MUX_1") (pin "2") (pinfunction "CTL_2") (pintype "bidirectional"))
    )
    (net (code "137") (name "/V_CTL_2") (class "Default")
      (node (ref "P2") (pin "15") (pinfunction "15_15") (pintype "passive"))
      (node (ref "VIDEO_MUX_2") (pin "2") (pinfunction "CTL_2") (pintype "bidirectional"))
    )
    (net (code "138") (name "/V_GND") (class "Default")
      (node (ref "SURFACE") (pin "2") (pinfunction "2_2") (pintype "bidirectional"))
      (node (ref "SURFACE") (pin "4") (pinfunction "4_4") (pintype "bidirectional"))
      (node (ref "V1") (pin "1") (pinfunction "1_1") (pintype "passive"))
      (node (ref "V2") (pin "1") (pinfunction "1_1") (pintype "passive"))
      (node (ref "V3") (pin "1") (pinfunction "1_1") (pintype "passive"))
      (node (ref "V4") (pin "1") (pinfunction "1_1") (pintype "passive"))
      (node (ref "VIDEO_MUX_1") (pin "4") (pinfunction "GND_4") (pintype "bidirectional"))
      (node (ref "VIDEO_MUX_2") (pin "4") (pinfunction "GND_4") (pintype "bidirectional"))
    )
    (net (code "139") (name "/V_IN1") (class "Default")
      (node (ref "C32") (pin "1") (pinfunction "1_1") (pintype "passive"))
      (node (ref "V1") (pin "2") (pinfunction "2_2") (pintype "passive"))
    )
    (net (code "140") (name "/V_IN2") (class "Default")
      (node (ref "C41") (pin "2") (pinfunction "2_2") (pintype "passive"))
      (node (ref "V2") (pin "2") (pinfunction "2_2") (pintype "passive"))
    )
    (net (code "141") (name "/V_IN3") (class "Default")
      (node (ref "C42") (pin "1") (pinfunction "1_1") (pintype "passive"))
      (node (ref "V3") (pin "2") (pinfunction "2_2") (pintype "passive"))
    )
    (net (code "142") (name "/V_IN4") (class "Default")
      (node (ref "C43") (pin "2") (pinfunction "2_2") (pintype "passive"))
      (node (ref "V4") (pin "2") (pinfunction "2_2") (pintype "passive"))
    )
    (net (code "143") (name "/Y") (class "Default")
      (node (ref "R15") (pin "2") (pinfunction "2_2") (pintype "passive"))
      (node (ref "SURFACE") (pin "5") (pinfunction "5_5") (pintype "bidirectional"))
      (node (ref "U5") (pin "5") (pinfunction "Y_5") (pintype "bidirectional"))
    )
    (net (code "144") (name "/Z") (class "Default")
      (node (ref "R15") (pin "1") (pinfunction "1_1") (pintype "passive"))
      (node (ref "SURFACE") (pin "6") (pinfunction "6_6") (pintype "bidirectional"))
      (node (ref "U5") (pin "6") (pinfunction "Z_6") (pintype "bidirectional"))
    )
    (net (code "145") (name "GND") (class "Default")
      (node (ref "C1") (pin "2") (pinfunction "2_2") (pintype "passive"))
      (node (ref "C17") (pin "2") (pinfunction "2_2") (pintype "passive"))
      (node (ref "C22") (pin "1") (pinfunction "1_1") (pintype "passive"))
      (node (ref "C44") (pin "2") (pinfunction "2_2") (pintype "passive"))
      (node (ref "C45") (pin "2") (pinfunction "2_2") (pintype "passive"))
      (node (ref "C50") (pin "2") (pinfunction "2_2") (pintype "passive"))
      (node (ref "H202") (pin "1") (pinfunction "1_1") (pintype "passive"))
      (node (ref "H203") (pin "1") (pinfunction "1_1") (pintype "passive"))
      (node (ref "H204") (pin "1") (pinfunction "1_1") (pintype "passive"))
      (node (ref "H2O1") (pin "1") (pinfunction "1_1") (pintype "passive"))
      (node (ref "IC1") (pin "5") (pinfunction "GND_5") (pintype "power_in"))
      (node (ref "IMU") (pin "3") (pinfunction "3_3") (pintype "passive"))
      (node (ref "P1") (pin "1") (pinfunction "1_1") (pintype "passive"))
      (node (ref "P1") (pin "2") (pinfunction "2_2") (pintype "passive"))
      (node (ref "P1") (pin "45") (pinfunction "45_45") (pintype "passive"))
      (node (ref "P1") (pin "49") (pinfunction "49_49") (pintype "passive"))
      (node (ref "P1") (pin "50") (pinfunction "50_50") (pintype "passive"))
      (node (ref "P2") (pin "1") (pinfunction "1_1") (pintype "passive"))
      (node (ref "P2") (pin "2") (pinfunction "2_2") (pintype "passive"))
      (node (ref "P2") (pin "49") (pinfunction "49_49") (pintype "passive"))
      (node (ref "P2") (pin "50") (pinfunction "50_50") (pintype "passive"))
      (node (ref "POWER_IN") (pin "1") (pinfunction "1_1") (pintype "passive"))
      (node (ref "R12") (pin "1") (pinfunction "1_1") (pintype "passive"))
      (node (ref "R13") (pin "2") (pinfunction "2_2") (pintype "passive"))
      (node (ref "R3") (pin "1") (pinfunction "1_1") (pintype "passive"))
      (node (ref "R6") (pin "1") (pinfunction "1_1") (pintype "passive"))
      (node (ref "R9") (pin "1") (pinfunction "1_1") (pintype "passive"))
      (node (ref "U1") (pin "1") (pinfunction "GND_1") (pintype "power_in"))
      (node (ref "U5") (pin "4") (pinfunction "GND_4") (pintype "power_in"))
      (node (ref "V1") (pin "4") (pinfunction "4_4") (pintype "passive"))
      (node (ref "V2") (pin "4") (pinfunction "4_4") (pintype "passive"))
      (node (ref "V3") (pin "4") (pinfunction "4_4") (pintype "passive"))
      (node (ref "V4") (pin "4") (pinfunction "4_4") (pintype "passive"))
      (node (ref "VIDEO_MUX_1") (pin "8") (pinfunction "GND_1_8") (pintype "bidirectional"))
      (node (ref "VIDEO_MUX_2") (pin "8") (pinfunction "GND_1_8") (pintype "bidirectional"))
      (node (ref "X1") (pin "49") (pinfunction "1_49") (pintype "passive"))
    )
    (net (code "146") (name "Net-(IC1A-A)") (class "Default")
      (node (ref "IC1") (pin "6") (pinfunction "A_6") (pintype "passive"))
      (node (ref "M1") (pin "2") (pinfunction "2_2") (pintype "passive"))
      (node (ref "M2") (pin "2") (pinfunction "2_2") (pintype "passive"))
      (node (ref "M3") (pin "2") (pinfunction "2_2") (pintype "passive"))
      (node (ref "M4") (pin "2") (pinfunction "2_2") (pintype "passive"))
      (node (ref "M5") (pin "2") (pinfunction "2_2") (pintype "passive"))
      (node (ref "M6") (pin "2") (pinfunction "2_2") (pintype "passive"))
      (node (ref "M7") (pin "2") (pinfunction "2_2") (pintype "passive"))
      (node (ref "M8") (pin "2") (pinfunction "2_2") (pintype "passive"))
      (node (ref "R14") (pin "1") (pinfunction "1_1") (pintype "passive"))
      (node (ref "R17") (pin "1") (pinfunction "1_1") (pintype "passive"))
    )
    (net (code "147") (name "Net-(IC1A-B)") (class "Default")
      (node (ref "IC1") (pin "7") (pinfunction "B_7") (pintype "passive"))
      (node (ref "M1") (pin "1") (pinfunction "1_1") (pintype "passive"))
      (node (ref "M2") (pin "1") (pinfunction "1_1") (pintype "passive"))
      (node (ref "M3") (pin "1") (pinfunction "1_1") (pintype "passive"))
      (node (ref "M4") (pin "1") (pinfunction "1_1") (pintype "passive"))
      (node (ref "M5") (pin "1") (pinfunction "1_1") (pintype "passive"))
      (node (ref "M6") (pin "1") (pinfunction "1_1") (pintype "passive"))
      (node (ref "M7") (pin "1") (pinfunction "1_1") (pintype "passive"))
      (node (ref "M8") (pin "1") (pinfunction "1_1") (pintype "passive"))
      (node (ref "R14") (pin "2") (pinfunction "2_2") (pintype "passive"))
      (node (ref "R17") (pin "2") (pinfunction "2_2") (pintype "passive"))
    )
    (net (code "148") (name "Net-(R1-Pad2)") (class "Default")
      (node (ref "R1") (pin "2") (pinfunction "2_2") (pintype "passive"))
      (node (ref "T1") (pin "B") (pinfunction "B_B") (pintype "passive"))
    )
    (net (code "149") (name "Net-(R4-Pad2)") (class "Default")
      (node (ref "R4") (pin "2") (pinfunction "2_2") (pintype "passive"))
      (node (ref "T2") (pin "B") (pinfunction "B_B") (pintype "passive"))
    )
    (net (code "150") (name "Net-(R7-Pad2)") (class "Default")
      (node (ref "R7") (pin "2") (pinfunction "2_2") (pintype "passive"))
      (node (ref "T3") (pin "B") (pinfunction "B_B") (pintype "passive"))
    )
    (net (code "151") (name "Net-(R10-Pad2)") (class "Default")
      (node (ref "R10") (pin "2") (pinfunction "2_2") (pintype "passive"))
      (node (ref "T4") (pin "B") (pinfunction "B_B") (pintype "passive"))
    )
    (net (code "152") (name "Net-(U1-*OUT0)") (class "Default")
      (node (ref "S0") (pin "2") (pinfunction "2_2") (pintype "passive"))
      (node (ref "U1") (pin "5") (pinfunction "*OUT0_5") (pintype "output"))
    )
    (net (code "153") (name "Net-(U1-*OUT1)") (class "Default")
      (node (ref "S1") (pin "2") (pinfunction "2_2") (pintype "passive"))
      (node (ref "U1") (pin "6") (pinfunction "*OUT1_6") (pintype "output"))
    )
    (net (code "154") (name "Net-(U1-*OUT2)") (class "Default")
      (node (ref "S2") (pin "2") (pinfunction "2_2") (pintype "passive"))
      (node (ref "U1") (pin "7") (pinfunction "*OUT2_7") (pintype "output"))
    )
    (net (code "155") (name "Net-(U1-*OUT3)") (class "Default")
      (node (ref "S3") (pin "2") (pinfunction "2_2") (pintype "passive"))
      (node (ref "U1") (pin "8") (pinfunction "*OUT3_8") (pintype "output"))
    )
    (net (code "156") (name "Net-(U1-*OUT4)") (class "Default")
      (node (ref "S4") (pin "2") (pinfunction "2_2") (pintype "passive"))
      (node (ref "U1") (pin "9") (pinfunction "*OUT4_9") (pintype "output"))
    )
    (net (code "157") (name "Net-(U1-*OUT5)") (class "Default")
      (node (ref "S5") (pin "2") (pinfunction "2_2") (pintype "passive"))
      (node (ref "U1") (pin "10") (pinfunction "*OUT5_10") (pintype "output"))
    )
    (net (code "158") (name "Net-(U1-*OUT6)") (class "Default")
      (node (ref "S6") (pin "2") (pinfunction "2_2") (pintype "passive"))
      (node (ref "U1") (pin "11") (pinfunction "*OUT6_11") (pintype "output"))
    )
    (net (code "159") (name "Net-(U1-*OUT7)") (class "Default")
      (node (ref "S7") (pin "2") (pinfunction "2_2") (pintype "passive"))
      (node (ref "U1") (pin "12") (pinfunction "*OUT7_12") (pintype "output"))
    )
    (net (code "160") (name "Net-(U1-R-EXT)") (class "Default")
      (node (ref "R13") (pin "1") (pinfunction "1_1") (pintype "passive"))
      (node (ref "U1") (pin "15") (pinfunction "R-EXT_15") (pintype "passive"))
    )
    (net (code "161") (name "Net-(U1-SDO)") (class "Default")
      (node (ref "C1") (pin "1") (pinfunction "1_1") (pintype "passive"))
      (node (ref "U1") (pin "14") (pinfunction "SDO_14") (pintype "output"))
    )
    (net (code "162") (name "Net-(VIDEO_MUX_1-IN_1)") (class "Default")
      (node (ref "C32") (pin "2") (pinfunction "2_2") (pintype "passive"))
      (node (ref "VIDEO_MUX_1") (pin "1") (pinfunction "IN_1_1") (pintype "bidirectional"))
    )
    (net (code "163") (name "Net-(VIDEO_MUX_1-IN_2)") (class "Default")
      (node (ref "C41") (pin "1") (pinfunction "1_1") (pintype "passive"))
      (node (ref "VIDEO_MUX_1") (pin "3") (pinfunction "IN_2_3") (pintype "bidirectional"))
    )
    (net (code "164") (name "Net-(VIDEO_MUX_2-IN_1)") (class "Default")
      (node (ref "C42") (pin "2") (pinfunction "2_2") (pintype "passive"))
      (node (ref "VIDEO_MUX_2") (pin "1") (pinfunction "IN_1_1") (pintype "bidirectional"))
    )
    (net (code "165") (name "Net-(VIDEO_MUX_2-IN_2)") (class "Default")
      (node (ref "C43") (pin "1") (pinfunction "1_1") (pintype "passive"))
      (node (ref "VIDEO_MUX_2") (pin "3") (pinfunction "IN_2_3") (pintype "bidirectional"))
    )
    (net (code "166") (name "unconnected-(VIDEO_MUX_2-NC-Pad5)") (class "Default")
      (node (ref "VIDEO_MUX_2") (pin "5") (pinfunction "NC_5") (pintype "bidirectional"))
    )
  )
)
